# MARS_FTDI.net
KiCad netlist of a schematic drawn in Altium Designer
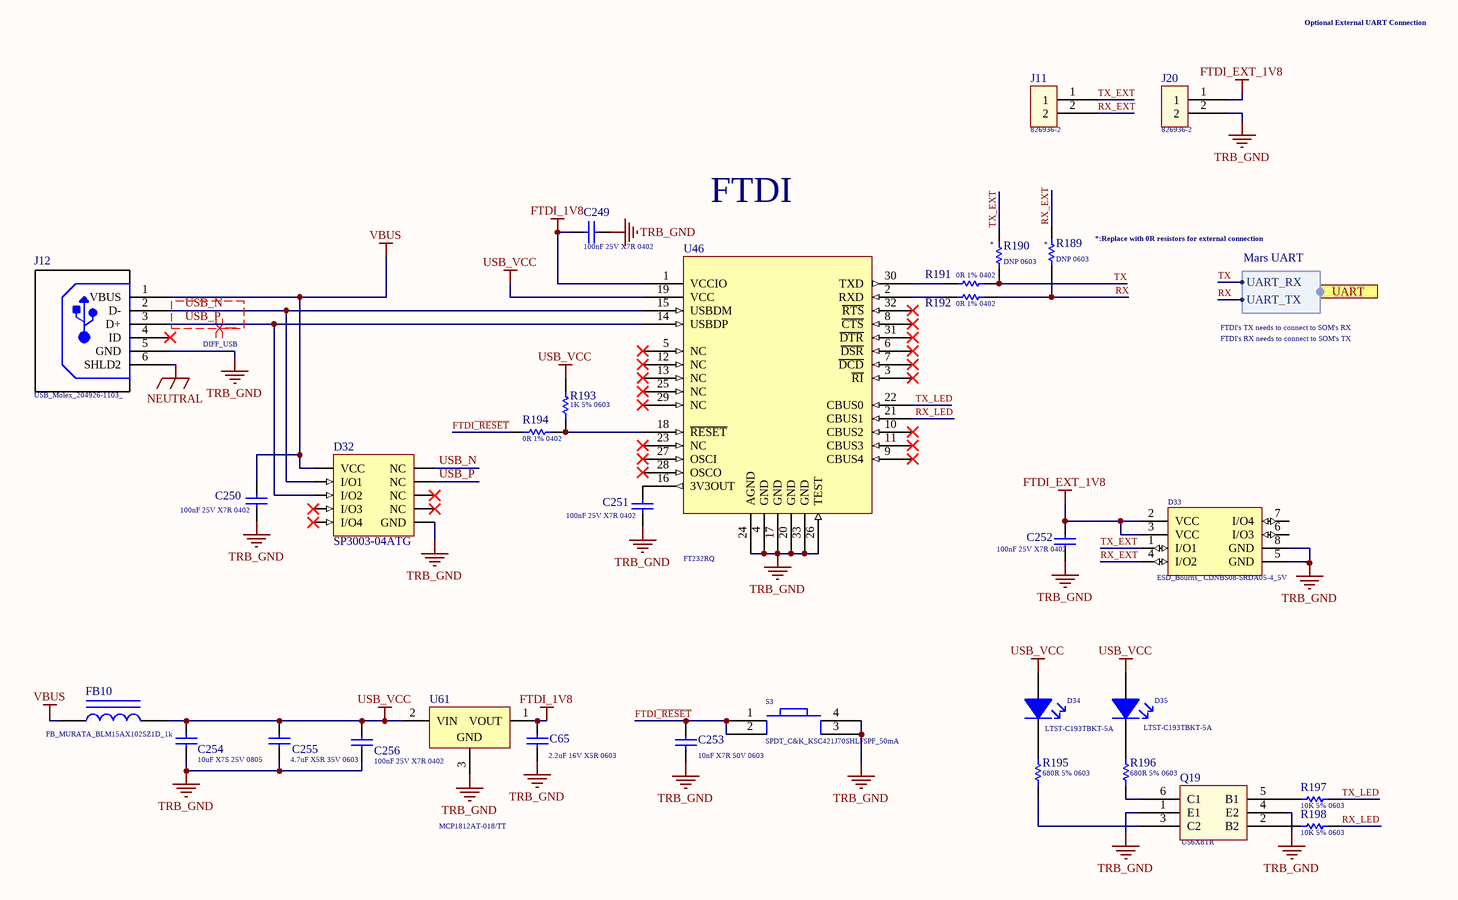
[diagram p0: MARS_FTDI.SchDoc]

(export (version "E")
  (design (tool "Eeschema 10.0.6"))
  (components
    (comp (ref "C65")
      (value "Cap_Taiyo_Yuden_2.2uF")
      (footprint "CAPC0603(1608)100_L")
      (description "CAP 2.2uF 16V ±10% 0603 (1608 Metric) Thickness 1mm SMD")
      (fields (field (name "TOLERANCE") "Â±10%") (field (name "CAPACITANCE") "2.2uF 16V X5R 0603"))
      (libsource (lib "Altium Content Vault") (part "CAP"))
    )
    (comp (ref "C249")
      (value "Cap_Taiyo_Yuden_TMK105B7104KV-FR_100nF")
      (footprint "Cap_Taiyo_Yuden_TMK105B7104KV-FR_100nF")
      (description "CAP CER 100nF 25V X7R 0402")
      (fields (field (name "CAPACITANCE") "100nF 25V X7R 0402"))
      (libsource (lib "Cap_Taiyo_Yuden_TMK105B7104KV-FR_100nF") (part "Cap_Taiyo_Yuden_TMK105B7104KV-FR_100nF"))
    )
    (comp (ref "C250")
      (value "Cap_Taiyo_Yuden_TMK105B7104KV-FR_100nF")
      (footprint "Cap_Taiyo_Yuden_TMK105B7104KV-FR_100nF")
      (description "CAP CER 100nF 25V X7R 0402")
      (fields (field (name "CAPACITANCE") "100nF 25V X7R 0402"))
      (libsource (lib "Cap_Taiyo_Yuden_TMK105B7104KV-FR_100nF") (part "Cap_Taiyo_Yuden_TMK105B7104KV-FR_100nF"))
    )
    (comp (ref "C251")
      (value "Cap_Taiyo_Yuden_TMK105B7104KV-FR_100nF")
      (footprint "Cap_Taiyo_Yuden_TMK105B7104KV-FR_100nF")
      (description "CAP CER 100nF 25V X7R 0402")
      (fields (field (name "CAPACITANCE") "100nF 25V X7R 0402"))
      (libsource (lib "Cap_Taiyo_Yuden_TMK105B7104KV-FR_100nF") (part "Cap_Taiyo_Yuden_TMK105B7104KV-FR_100nF"))
    )
    (comp (ref "C252")
      (value "Cap_Taiyo_Yuden_TMK105B7104KV-FR_100nF")
      (footprint "Cap_Taiyo_Yuden_TMK105B7104KV-FR_100nF")
      (description "CAP CER 100nF 25V X7R 0402")
      (fields (field (name "CAPACITANCE") "100nF 25V X7R 0402"))
      (libsource (lib "Cap_Taiyo_Yuden_TMK105B7104KV-FR_100nF") (part "Cap_Taiyo_Yuden_TMK105B7104KV-FR_100nF"))
    )
    (comp (ref "C253")
      (value "Cap_Kemet_C0603C103J5RACTU_eec")
      (footprint "Kemet_C0603_0")
      (description "CAP CER 10nF 50V X7R 0603")
      (fields
        (field (name "PART NUMBER") "C0603C103J5RACTU")
        (field (name "MANUFACTURER") "Kemet")
        (field (name "CAPACITANCE") "10nF X7R 50V 0603")
      )
      (libsource (lib "Cap_Kemet_C0603C103J5RACTU_10nF") (part "Cap_Kemet_C0603C103J5RACTU_eec"))
    )
    (comp (ref "C254")
      (value "Cap_Murata_ GRM21BC71E106ME11L_10uF")
      (footprint "Cap_Murata_ GRM21BC71E106ME11L_10uF")
      (description "CAP CER 10uF 25V X7R 0805")
      (fields (field (name "CAPACITANCE") "10uF X7S 25V 0805"))
      (libsource (lib "Cap_Murata_ GRM21BC71E106ME11L_10uF") (part "Cap_Murata_ GRM21BC71E106ME11L_10uF"))
    )
    (comp (ref "C255")
      (value "Cap_Murata_ZRB18AR6YA475ME05L_4.7uF")
      (footprint "Cap_Murata_ZRB18AR6YA475ME05L_4.7uF")
      (description "CAP CER 4.7uF 35V X5R 0603")
      (fields (field (name "CAPACITANCE") "4.7uF X5R 35V 0603"))
      (libsource (lib "Cap_Murata_ZRB18AR6YA475ME05L_4.7uF") (part "Cap_Murata_ZRB18AR6YA475ME05L_4.7uF"))
    )
    (comp (ref "C256")
      (value "Cap_Taiyo_Yuden_TMK105B7104KV-FR_100nF")
      (footprint "Cap_Taiyo_Yuden_TMK105B7104KV-FR_100nF")
      (description "CAP CER 100nF 25V X7R 0402")
      (fields (field (name "CAPACITANCE") "100nF 25V X7R 0402"))
      (libsource (lib "Cap_Taiyo_Yuden_TMK105B7104KV-FR_100nF") (part "Cap_Taiyo_Yuden_TMK105B7104KV-FR_100nF"))
    )
    (comp (ref "D32")
      (value "Diode_SP3003-04ATG_LVDS_ESD")
      (footprint "Diode_SP3003-04ATG_LVDS_ESD")
      (description "ESD Suppressors / TVS Diodes 4 Ch 8kV 0.65pF SPA")
      (fields (field (name "SERIES") "SP3003-04ATG"))
      (libsource (lib "Diode_SP3003-04ATG_LVDS_ESD") (part "Diode_SP3003-04ATG_LVDS_ESD"))
    )
    (comp (ref "D33")
      (value "ESD_Bourns_ CDNBS08-SRDA05-4_5V")
      (footprint "ESD_Bourns_ CDNBS08-SRDA05-4_5V")
      (description "ESD Suppressors / TVS Diodes SO-8 5V 500W Low Capacitance")
      (libsource (lib "ESD_Bourns_ CDNBS08-SRDA05-4_5V") (part "ESD_Bourns_ CDNBS08-SRDA05-4_5V"))
    )
    (comp (ref "D34")
      (value "Led_Lite-On_LTST-C193TBKT-5A_Blue")
      (footprint "Led_Lite-On_LTST-C193TBKT-5A_Blue")
      (description "Standard LEDs - SMD Blue 470nm 28mcd 20mA")
      (fields (field (name "SERIES") "LTST-C193TBKT-5A"))
      (libsource (lib "Led_Lite-On_LTST-C193TBKT-5A_Blue") (part "Led_Lite-On_LTST-C193TBKT-5A_Blue"))
    )
    (comp (ref "D35")
      (value "Led_Lite-On_LTST-C193TBKT-5A_Blue")
      (footprint "Led_Lite-On_LTST-C193TBKT-5A_Blue")
      (description "Standard LEDs - SMD Blue 470nm 28mcd 20mA")
      (fields (field (name "SERIES") "LTST-C193TBKT-5A"))
      (libsource (lib "Led_Lite-On_LTST-C193TBKT-5A_Blue") (part "Led_Lite-On_LTST-C193TBKT-5A_Blue"))
    )
    (comp (ref "FB10")
      (value "FB_MURATA_BLM15AX102SZ1D_1k")
      (footprint "FB_MURATA_BLM15AX102SZ1D_1k")
      (description "FB SMD 1000 OHM 25% 3/4W 0402")
      (libsource (lib "FB_MURATA_BLM15AX102SZ1D_1k") (part "FB_MURATA_BLM15AX102SZ1D_1k"))
    )
    (comp (ref "J11")
      (value "Header_TE_Connectivity_826936-2_2POS_5A")
      (footprint "Header_TE_Connectivity_826936-2_2POS_5A")
      (description "Headers & Wire Housings 2P SINGLE ROW 5A")
      (fields (field (name "SERIES") "826936-2"))
      (libsource (lib "Header_TE_Connectivity_826936-2_2POS_5A") (part "Header_TE_Connectivity_826936-2_2POS_5A"))
    )
    (comp (ref "J12")
      (value "USB_Molex_204926-1103_")
      (footprint "USB_Molex_204926-1103")
      (description "USB Connectors MicroUSB B Rec SMT WOut Flange WtrProf")
      (libsource (lib "USB_Molex_204926-1103") (part "USB_Molex_204926-1103"))
    )
    (comp (ref "J20")
      (value "Header_TE_Connectivity_826936-2_2POS_5A")
      (footprint "Header_TE_Connectivity_826936-2_2POS_5A")
      (description "Headers & Wire Housings 2P SINGLE ROW 5A")
      (fields (field (name "SERIES") "826936-2"))
      (libsource (lib "Header_TE_Connectivity_826936-2_2POS_5A") (part "Header_TE_Connectivity_826936-2_2POS_5A"))
    )
    (comp (ref "Q19")
      (value "BJT_ROHM_US6X8TR_1A_NPN")
      (footprint "BJT_ROHM_US6X8TR_1A_NPN")
      (description "Bipolar Transistors - BJT NPN+NPN 30VCEO 1A SOT-363T")
      (fields (field (name "SERIES") "US6X8TR"))
      (libsource (lib "BJT_ROHM_US6X8TR_1A_NPN") (part "BJT_ROHM_US6X8TR_1A_NPN"))
    )
    (comp (ref "R189")
      (value "RES_DNP_0603")
      (footprint "RES_DNP_0603")
      (description "0603 Do not place resistor")
      (fields (field (name "RESISTANCE") "DNP 0603"))
      (libsource (lib "RES_DNP_0603") (part "RES_DNP_0603"))
    )
    (comp (ref "R190")
      (value "RES_DNP_0603")
      (footprint "RES_DNP_0603")
      (description "0603 Do not place resistor")
      (fields (field (name "RESISTANCE") "DNP 0603"))
      (libsource (lib "RES_DNP_0603") (part "RES_DNP_0603"))
    )
    (comp (ref "R191")
      (value "Res_Vishay_CRCW04020000Z0EDC_0_Ohm")
      (footprint "Res_Vishay_CRCW04020000Z0EDC_0_Ohm")
      (description "0R 0.062W 1% 0402 (1005 Metric)  SMD")
      (fields (field (name "RESISTANCE") "0R 1% 0402"))
      (libsource (lib "Res_Vishay_CRCW04020000Z0EDC_0_Ohm") (part "Res_Vishay_CRCW04020000Z0EDC_0_Ohm"))
    )
    (comp (ref "R192")
      (value "Res_Vishay_CRCW04020000Z0EDC_0_Ohm")
      (footprint "Res_Vishay_CRCW04020000Z0EDC_0_Ohm")
      (description "0R 0.062W 1% 0402 (1005 Metric)  SMD")
      (fields (field (name "RESISTANCE") "0R 1% 0402"))
      (libsource (lib "Res_Vishay_CRCW04020000Z0EDC_0_Ohm") (part "Res_Vishay_CRCW04020000Z0EDC_0_Ohm"))
    )
    (comp (ref "R193")
      (value "1K 5% 0603")
      (footprint "RESC0603(1608)_L")
      (description "1K 0.1W 5% 0603 (1608 Metric)  SMD")
      (fields (field (name "TOLERANCE") "5 %") (field (name "POWER") "0.1 W"))
      (libsource (lib "Altium Content Vault") (part "RES"))
    )
    (comp (ref "R194")
      (value "Res_Vishay_CRCW04020000Z0EDC_0_Ohm")
      (footprint "Res_Vishay_CRCW04020000Z0EDC_0_Ohm")
      (description "0R 0.062W 1% 0402 (1005 Metric)  SMD")
      (fields (field (name "RESISTANCE") "0R 1% 0402"))
      (libsource (lib "Res_Vishay_CRCW04020000Z0EDC_0_Ohm") (part "Res_Vishay_CRCW04020000Z0EDC_0_Ohm"))
    )
    (comp (ref "R195")
      (value "680R 5% 0603")
      (footprint "RESC0603(1608)_L")
      (description "680R 0.1W 5% 0603 (1608 Metric)  SMD")
      (fields (field (name "TOLERANCE") "5 %") (field (name "POWER") "0.1 W"))
      (libsource (lib "Altium Content Vault") (part "RES"))
    )
    (comp (ref "R196")
      (value "680R 5% 0603")
      (footprint "RESC0603(1608)_L")
      (description "680R 0.1W 5% 0603 (1608 Metric)  SMD")
      (fields (field (name "TOLERANCE") "5 %") (field (name "POWER") "0.1 W"))
      (libsource (lib "Altium Content Vault") (part "RES"))
    )
    (comp (ref "R197")
      (value "10K 5% 0603")
      (footprint "RESC0603(1608)_L")
      (description "10K 0.1W 5% 0603 (1608 Metric)  SMD")
      (fields (field (name "TOLERANCE") "5 %") (field (name "POWER") "0.1 W"))
      (libsource (lib "Altium Content Vault") (part "RES"))
    )
    (comp (ref "R198")
      (value "10K 5% 0603")
      (footprint "RESC0603(1608)_L")
      (description "10K 0.1W 5% 0603 (1608 Metric)  SMD")
      (fields (field (name "TOLERANCE") "5 %") (field (name "POWER") "0.1 W"))
      (libsource (lib "Altium Content Vault") (part "RES"))
    )
    (comp (ref "S3")
      (value "SPDT_C&K_KSC421J70SHLFSPF_50mA")
      (footprint "SPDT_C&K_KSC421J70SHLFSPF_50mA")
      (description "Tactile Switches Tact 6.2 x 6.2, 5.1 mm H, 1.7N, J leads, Potting Friendly, IP67")
      (libsource (lib "SPDT_C&K_KSC421J70SHLFSPF_50mA") (part "SPDT_C&K_KSC421J70SHLFSPF_50mA"))
    )
    (comp (ref "U46")
      (value "IC_FTDI_FT232RQ-REEL")
      (footprint "IC_FTDI_FT232RQ-REEL")
      (description "USB Interface IC USB to Serial UART Enhanced IC QFN-32")
      (fields (field (name "SERIES") "FT232RQ"))
      (libsource (lib "IC_FTDI_FT232RQ-REEL") (part "IC_FTDI_FT232RQ-REEL"))
    )
    (comp (ref "U61")
      (value "LDO_Microchip_MCP1812AT-018_1V8")
      (footprint "LDO_Microchip_MCP1812AT-018_1V8")
      (description "LDO Voltage Regulators Ultra Low Iq LDO")
      (fields (field (name "SERIES") "MCP1812AT-018/TT"))
      (libsource (lib "LDO_Microchip_MCP1812AT-018_1V8") (part "LDO_Microchip_MCP1812AT-018_1V8"))
    )
  )
  (nets
    (net (code "3") (name "/FTDI~{_RESET}") (class "Default")
      (node (ref "C253") (pin "1") (pinfunction "1_1") (pintype "passive"))
      (node (ref "R194") (pin "2") (pinfunction "2_2") (pintype "passive"))
      (node (ref "S3") (pin "1") (pintype "passive"))
      (node (ref "S3") (pin "2") (pintype "passive"))
    )
    (net (code "4") (name "/RX") (class "Default")
      (node (ref "R189") (pin "2") (pinfunction "2_2") (pintype "passive"))
      (node (ref "R192") (pin "2") (pinfunction "2_2") (pintype "passive"))
    )
    (net (code "5") (name "/RX_EXT") (class "Default")
      (node (ref "D33") (pin "4") (pinfunction "I/O2_4") (pintype "bidirectional"))
      (node (ref "J11") (pin "2") (pinfunction "2_2") (pintype "passive"))
      (node (ref "R189") (pin "1") (pinfunction "1_1") (pintype "passive"))
    )
    (net (code "6") (name "/RX_LED") (class "Default")
      (node (ref "R198") (pin "1") (pinfunction "1_1") (pintype "passive"))
      (node (ref "U46") (pin "21") (pinfunction "CBUS1_21") (pintype "input"))
    )
    (net (code "7") (name "/TX") (class "Default")
      (node (ref "R190") (pin "2") (pinfunction "2_2") (pintype "passive"))
      (node (ref "R191") (pin "2") (pinfunction "2_2") (pintype "passive"))
    )
    (net (code "8") (name "/TX_EXT") (class "Default")
      (node (ref "D33") (pin "1") (pinfunction "I/O1_1") (pintype "bidirectional"))
      (node (ref "J11") (pin "1") (pinfunction "1_1") (pintype "passive"))
      (node (ref "R190") (pin "1") (pinfunction "1_1") (pintype "passive"))
    )
    (net (code "9") (name "/TX_LED") (class "Default")
      (node (ref "R197") (pin "2") (pinfunction "2_2") (pintype "passive"))
      (node (ref "U46") (pin "22") (pinfunction "CBUS0_22") (pintype "input"))
    )
    (net (code "10") (name "/USB_N") (class "Default")
      (node (ref "D32") (pin "1") (pinfunction "I/O1_1") (pintype "input"))
      (node (ref "D32") (pin "10") (pinfunction "NC_10") (pintype "tri_state"))
      (node (ref "J12") (pin "2") (pinfunction "D-_2") (pintype "passive"))
      (node (ref "U46") (pin "15") (pinfunction "USBDM_15") (pintype "input"))
    )
    (net (code "11") (name "/USB_P") (class "Default")
      (node (ref "D32") (pin "2") (pinfunction "I/O2_2") (pintype "input"))
      (node (ref "D32") (pin "9") (pinfunction "NC_9") (pintype "tri_state"))
      (node (ref "J12") (pin "3") (pinfunction "D+_3") (pintype "passive"))
      (node (ref "U46") (pin "14") (pinfunction "USBDP_14") (pintype "input"))
    )
    (net (code "13") (name "FTDI_1V8") (class "Default")
      (node (ref "C249") (pin "2") (pinfunction "2_2") (pintype "passive"))
      (node (ref "C65") (pin "2") (pinfunction "2_2") (pintype "passive"))
      (node (ref "U46") (pin "1") (pinfunction "VCCIO_1") (pintype "power_in"))
      (node (ref "U61") (pin "1") (pinfunction "VOUT_1") (pintype "power_in"))
    )
    (net (code "14") (name "FTDI_EXT_1V8") (class "Default")
      (node (ref "C252") (pin "2") (pinfunction "2_2") (pintype "passive"))
      (node (ref "D33") (pin "2") (pinfunction "VCC_2") (pintype "power_in"))
      (node (ref "D33") (pin "3") (pinfunction "VCC_3") (pintype "power_in"))
      (node (ref "J20") (pin "1") (pinfunction "1_1") (pintype "passive"))
    )
    (net (code "15") (name "NEUTRAL") (class "Default")
      (node (ref "J12") (pin "6") (pinfunction "SHLD2_6") (pintype "passive"))
    )
    (net (code "16") (name "Net-(D34-K)") (class "Default")
      (node (ref "D34") (pin "1") (pinfunction "K_1") (pintype "passive"))
      (node (ref "R195") (pin "2") (pinfunction "2_2") (pintype "passive"))
    )
    (net (code "17") (name "Net-(D35-K)") (class "Default")
      (node (ref "D35") (pin "1") (pinfunction "K_1") (pintype "passive"))
      (node (ref "R196") (pin "2") (pinfunction "2_2") (pintype "passive"))
    )
    (net (code "18") (name "Net-(Q19-B1)") (class "Default")
      (node (ref "Q19") (pin "5") (pinfunction "B1_5") (pintype "passive"))
      (node (ref "R197") (pin "1") (pinfunction "1_1") (pintype "passive"))
    )
    (net (code "19") (name "Net-(Q19-B2)") (class "Default")
      (node (ref "Q19") (pin "2") (pinfunction "B2_2") (pintype "passive"))
      (node (ref "R198") (pin "2") (pinfunction "2_2") (pintype "passive"))
    )
    (net (code "20") (name "Net-(Q19-C1)") (class "Default")
      (node (ref "Q19") (pin "6") (pinfunction "C1_6") (pintype "passive"))
      (node (ref "R196") (pin "1") (pinfunction "1_1") (pintype "passive"))
    )
    (net (code "21") (name "Net-(Q19-C2)") (class "Default")
      (node (ref "Q19") (pin "3") (pinfunction "C2_3") (pintype "passive"))
      (node (ref "R195") (pin "1") (pinfunction "1_1") (pintype "passive"))
    )
    (net (code "22") (name "Net-(U46-3V3OUT)") (class "Default")
      (node (ref "C251") (pin "2") (pinfunction "2_2") (pintype "passive"))
      (node (ref "U46") (pin "16") (pinfunction "3V3OUT_16") (pintype "output"))
    )
    (net (code "23") (name "Net-(U46-RXD)") (class "Default")
      (node (ref "R192") (pin "1") (pinfunction "1_1") (pintype "passive"))
      (node (ref "U46") (pin "2") (pinfunction "RXD_2") (pintype "input"))
    )
    (net (code "24") (name "Net-(U46-TXD)") (class "Default")
      (node (ref "R191") (pin "1") (pinfunction "1_1") (pintype "passive"))
      (node (ref "U46") (pin "30") (pinfunction "TXD_30") (pintype "output"))
    )
    (net (code "25") (name "Net-(U46-~{RESET})") (class "Default")
      (node (ref "R193") (pin "1") (pinfunction "1_1") (pintype "passive"))
      (node (ref "R194") (pin "1") (pinfunction "1_1") (pintype "passive"))
      (node (ref "U46") (pin "18") (pinfunction "~{RESET}_18") (pintype "input"))
    )
    (net (code "26") (name "TRB_GND") (class "Default")
      (node (ref "C249") (pin "1") (pinfunction "1_1") (pintype "passive"))
      (node (ref "C250") (pin "1") (pinfunction "1_1") (pintype "passive"))
      (node (ref "C251") (pin "1") (pinfunction "1_1") (pintype "passive"))
      (node (ref "C252") (pin "1") (pinfunction "1_1") (pintype "passive"))
      (node (ref "C253") (pin "2") (pinfunction "2_2") (pintype "passive"))
      (node (ref "C254") (pin "2") (pinfunction "2_2") (pintype "passive"))
      (node (ref "C255") (pin "1") (pinfunction "1_1") (pintype "passive"))
      (node (ref "C256") (pin "1") (pinfunction "1_1") (pintype "passive"))
      (node (ref "C65") (pin "1") (pinfunction "1_1") (pintype "passive"))
      (node (ref "D32") (pin "8") (pinfunction "GND_8") (pintype "power_in"))
      (node (ref "D33") (pin "5") (pinfunction "GND_5") (pintype "power_in"))
      (node (ref "D33") (pin "8") (pinfunction "GND_8") (pintype "power_in"))
      (node (ref "J12") (pin "5") (pinfunction "GND_5") (pintype "passive"))
      (node (ref "J20") (pin "2") (pinfunction "2_2") (pintype "passive"))
      (node (ref "Q19") (pin "1") (pinfunction "E1_1") (pintype "passive"))
      (node (ref "Q19") (pin "4") (pinfunction "E2_4") (pintype "passive"))
      (node (ref "S3") (pin "3") (pintype "passive"))
      (node (ref "S3") (pin "4") (pintype "passive"))
      (node (ref "U46") (pin "17") (pinfunction "GND_17") (pintype "power_in"))
      (node (ref "U46") (pin "20") (pinfunction "GND_20") (pintype "power_in"))
      (node (ref "U46") (pin "24") (pinfunction "AGND_24") (pintype "power_in"))
      (node (ref "U46") (pin "26") (pinfunction "TEST_26") (pintype "input"))
      (node (ref "U46") (pin "33") (pinfunction "GND_33") (pintype "power_in"))
      (node (ref "U46") (pin "4") (pinfunction "GND_4") (pintype "power_in"))
      (node (ref "U61") (pin "3") (pinfunction "GND_3") (pintype "power_in"))
    )
    (net (code "27") (name "USB_VCC") (class "Default")
      (node (ref "C254") (pin "1") (pinfunction "1_1") (pintype "passive"))
      (node (ref "C255") (pin "2") (pinfunction "2_2") (pintype "passive"))
      (node (ref "C256") (pin "2") (pinfunction "2_2") (pintype "passive"))
      (node (ref "D34") (pin "2") (pinfunction "A_2") (pintype "passive"))
      (node (ref "D35") (pin "2") (pinfunction "A_2") (pintype "passive"))
      (node (ref "FB10") (pin "2") (pinfunction "2_2") (pintype "passive"))
      (node (ref "R193") (pin "2") (pinfunction "2_2") (pintype "passive"))
      (node (ref "U46") (pin "19") (pinfunction "VCC_19") (pintype "power_in"))
      (node (ref "U61") (pin "2") (pinfunction "VIN_2") (pintype "power_in"))
    )
    (net (code "28") (name "VBUS") (class "Default")
      (node (ref "C250") (pin "2") (pinfunction "2_2") (pintype "passive"))
      (node (ref "D32") (pin "3") (pinfunction "VCC_3") (pintype "passive"))
      (node (ref "FB10") (pin "1") (pinfunction "1_1") (pintype "passive"))
      (node (ref "J12") (pin "1") (pinfunction "VBUS_1") (pintype "passive"))
    )
    (net (code "29") (name "unconnected-(D32-I{slash}O3-Pad4)") (class "Default")
      (node (ref "D32") (pin "4") (pinfunction "I/O3_4") (pintype "input+no_connect"))
    )
    (net (code "30") (name "unconnected-(D32-I{slash}O4-Pad5)") (class "Default")
      (node (ref "D32") (pin "5") (pinfunction "I/O4_5") (pintype "input+no_connect"))
    )
    (net (code "31") (name "unconnected-(D32-NC-Pad6)") (class "Default")
      (node (ref "D32") (pin "6") (pinfunction "NC_6") (pintype "tri_state+no_connect"))
    )
    (net (code "32") (name "unconnected-(D32-NC-Pad7)") (class "Default")
      (node (ref "D32") (pin "7") (pinfunction "NC_7") (pintype "tri_state+no_connect"))
    )
    (net (code "33") (name "unconnected-(D33-I{slash}O3-Pad6)") (class "Default")
      (node (ref "D33") (pin "6") (pinfunction "I/O3_6") (pintype "bidirectional"))
    )
    (net (code "34") (name "unconnected-(D33-I{slash}O4-Pad7)") (class "Default")
      (node (ref "D33") (pin "7") (pinfunction "I/O4_7") (pintype "bidirectional"))
    )
    (net (code "35") (name "unconnected-(J12-ID-Pad4)") (class "Default")
      (node (ref "J12") (pin "4") (pinfunction "ID_4") (pintype "passive+no_connect"))
    )
    (net (code "36") (name "unconnected-(U46-CBUS2-Pad10)") (class "Default")
      (node (ref "U46") (pin "10") (pinfunction "CBUS2_10") (pintype "input+no_connect"))
    )
    (net (code "37") (name "unconnected-(U46-CBUS3-Pad11)") (class "Default")
      (node (ref "U46") (pin "11") (pinfunction "CBUS3_11") (pintype "input+no_connect"))
    )
    (net (code "38") (name "unconnected-(U46-CBUS4-Pad9)") (class "Default")
      (node (ref "U46") (pin "9") (pinfunction "CBUS4_9") (pintype "input+no_connect"))
    )
    (net (code "39") (name "unconnected-(U46-NC-Pad5)") (class "Default")
      (node (ref "U46") (pin "5") (pinfunction "NC_5") (pintype "input+no_connect"))
    )
    (net (code "40") (name "unconnected-(U46-NC-Pad12)") (class "Default")
      (node (ref "U46") (pin "12") (pinfunction "NC_12") (pintype "input+no_connect"))
    )
    (net (code "41") (name "unconnected-(U46-NC-Pad13)") (class "Default")
      (node (ref "U46") (pin "13") (pinfunction "NC_13") (pintype "input+no_connect"))
    )
    (net (code "42") (name "unconnected-(U46-NC-Pad23)") (class "Default")
      (node (ref "U46") (pin "23") (pinfunction "NC_23") (pintype "input+no_connect"))
    )
    (net (code "43") (name "unconnected-(U46-NC-Pad25)") (class "Default")
      (node (ref "U46") (pin "25") (pinfunction "NC_25") (pintype "input+no_connect"))
    )
    (net (code "44") (name "unconnected-(U46-NC-Pad29)") (class "Default")
      (node (ref "U46") (pin "29") (pinfunction "NC_29") (pintype "input+no_connect"))
    )
    (net (code "45") (name "unconnected-(U46-OSCI-Pad27)") (class "Default")
      (node (ref "U46") (pin "27") (pinfunction "OSCI_27") (pintype "input+no_connect"))
    )
    (net (code "46") (name "unconnected-(U46-OSCO-Pad28)") (class "Default")
      (node (ref "U46") (pin "28") (pinfunction "OSCO_28") (pintype "input+no_connect"))
    )
    (net (code "47") (name "unconnected-(U46-~{CTS}-Pad8)") (class "Default")
      (node (ref "U46") (pin "8") (pinfunction "~{CTS}_8") (pintype "input+no_connect"))
    )
    (net (code "48") (name "unconnected-(U46-~{DCD}-Pad7)") (class "Default")
      (node (ref "U46") (pin "7") (pinfunction "~{DCD}_7") (pintype "input+no_connect"))
    )
    (net (code "49") (name "unconnected-(U46-~{DSR}-Pad6)") (class "Default")
      (node (ref "U46") (pin "6") (pinfunction "~{DSR}_6") (pintype "input+no_connect"))
    )
    (net (code "50") (name "unconnected-(U46-~{DTR}-Pad31)") (class "Default")
      (node (ref "U46") (pin "31") (pinfunction "~{DTR}_31") (pintype "input+no_connect"))
    )
    (net (code "51") (name "unconnected-(U46-~{RI}-Pad3)") (class "Default")
      (node (ref "U46") (pin "3") (pinfunction "~{RI}_3") (pintype "input+no_connect"))
    )
    (net (code "52") (name "unconnected-(U46-~{RTS}-Pad32)") (class "Default")
      (node (ref "U46") (pin "32") (pinfunction "~{RTS}_32") (pintype "input+no_connect"))
    )
  )
)
